# Fan_Motor_Driver.net
KiCad netlist of a schematic drawn in Altium Designer
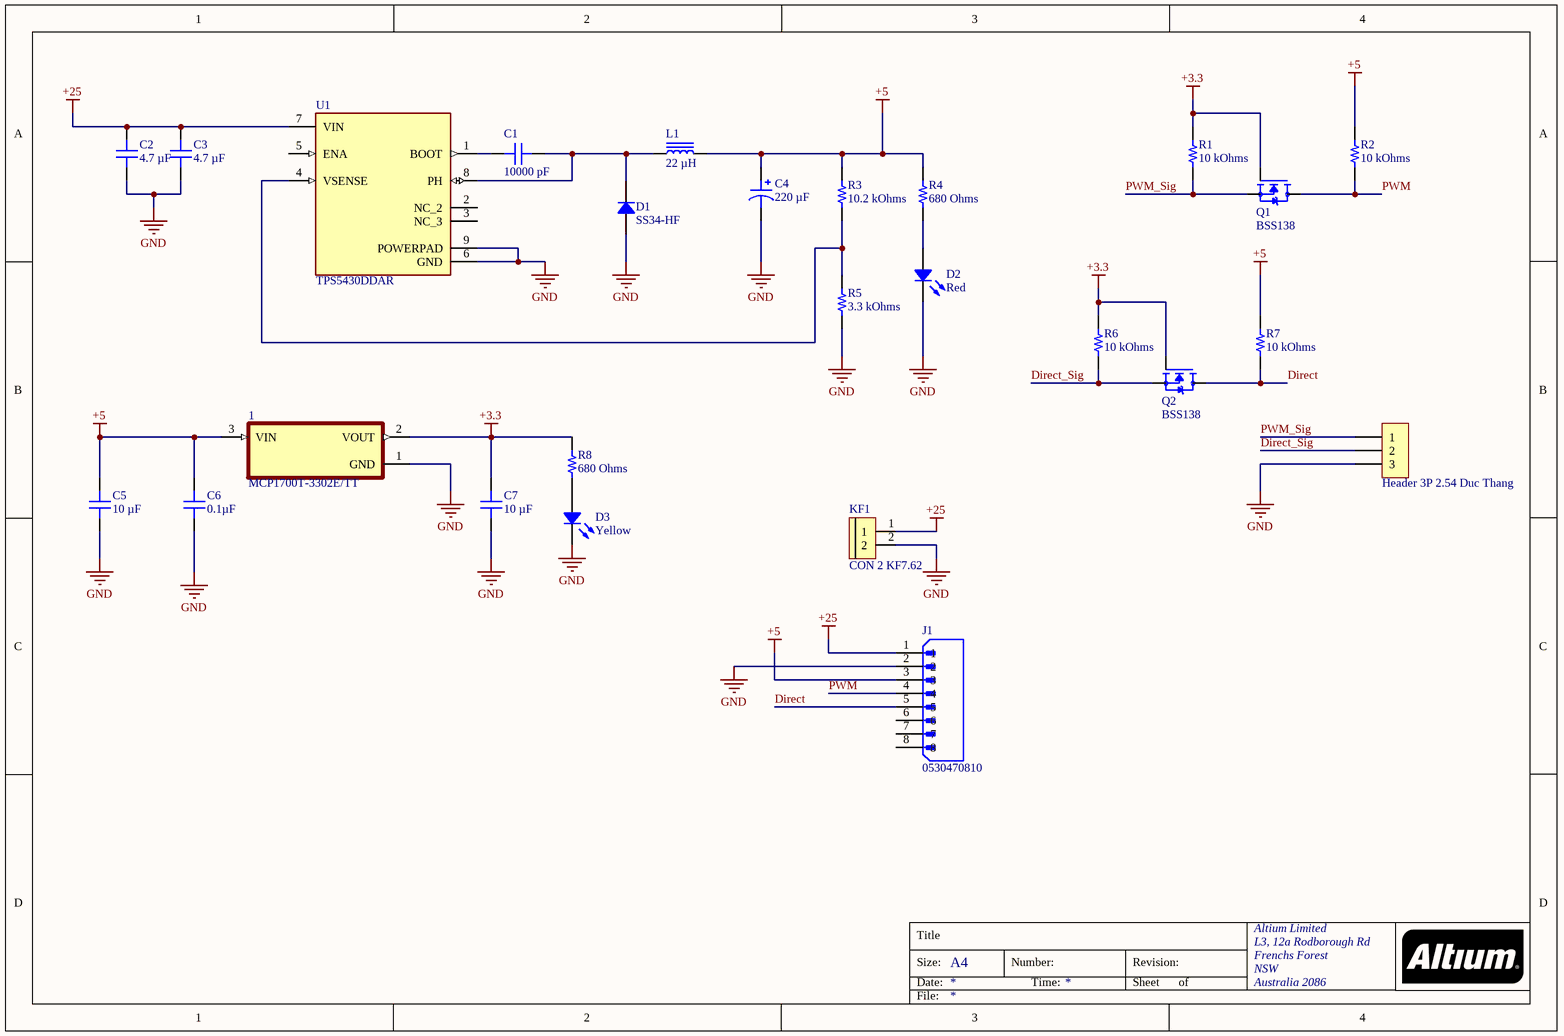
[diagram p0: Fan_Motor_Driver.SchDoc]

(export (version "E")
  (design (tool "Eeschema 10.0.6"))
  (components
    (comp (ref "1")
      (value "MCP1700T-3302E/TT")
      (footprint "SOT95P237X112-3N")
      (description "Linear Voltage Regulator IC 1 Output 250mA SOT-23-3")
      (fields (field (name "MF") "Microchip"))
      (libsource (lib "MCP1700T-3302E_TT") (part "MCP1700T-3302E/TT"))
    )
    (comp (ref "C1")
      (value "10000 pF")
      (footprint "CAP 0603_1608")
      (description "CAP CER 0603 10NF 16V X7R 10%")
      (fields (field (name "PART NUMBER") "C0603C103K4RECAUTO") (field (name "MANUFACTURER") "KEMET"))
      (libsource (lib "Celestial Altium Library - altium_library") (part "Capacitor"))
    )
    (comp (ref "C2")
      (value "4.7 µF")
      (footprint "CAP 0805_2012")
      (description "CAP CER 4.7UF 25V X7R 0805")
      (fields (field (name "PART NUMBER") "KGM21AR71E475KU") (field (name "MANUFACTURER") "KYOCERA AVX"))
      (libsource (lib "Celestial Altium Library - altium_library") (part "Capacitor"))
    )
    (comp (ref "C3")
      (value "4.7 µF")
      (footprint "CAP 0805_2012")
      (description "CAP CER 4.7UF 25V X7R 0805")
      (fields (field (name "PART NUMBER") "KGM21AR71E475KU") (field (name "MANUFACTURER") "KYOCERA AVX"))
      (libsource (lib "Celestial Altium Library - altium_library") (part "Capacitor"))
    )
    (comp (ref "C4")
      (value "220 µF")
      (footprint "CAP ALSMD 6.6MM H6.1MM")
      (description "CAP ALUM 220UF 20% 10V SMD")
      (fields
        (field (name "PART NUMBER") "EEE-FT1A221AL")
        (field (name "MANUFACTURER") "Panasonic Electronic Components")
      )
      (libsource (lib "Celestial Altium Library - altium_library") (part "Polarised Capacitor"))
    )
    (comp (ref "C5")
      (value "10 µF")
      (footprint "CAP 0805_2012")
      (description "CAP CER 10UF 16V X6S 0805")
      (fields
        (field (name "PART NUMBER") "C2012X6S1C106K125AC")
        (field (name "MANUFACTURER") "TDK Corporation")
      )
      (libsource (lib "Celestial Altium Library - altium_library") (part "Capacitor"))
    )
    (comp (ref "C6")
      (value "0.1µF")
      (footprint "CAP 0603_1608")
      (description "CAP CER 0.1UF 16V X7R 0603")
      (fields (field (name "PART NUMBER") "0603YC104K4T4A") (field (name "MANUFACTURER") "AVX Corporation"))
      (libsource (lib "Celestial Altium Library - altium_library") (part "Capacitor"))
    )
    (comp (ref "C7")
      (value "10 µF")
      (footprint "CAP 0805_2012")
      (description "CAP CER 10UF 16V X6S 0805")
      (fields
        (field (name "PART NUMBER") "C2012X6S1C106K125AC")
        (field (name "MANUFACTURER") "TDK Corporation")
      )
      (libsource (lib "Celestial Altium Library - altium_library") (part "Capacitor"))
    )
    (comp (ref "D1")
      (value "SS34-HF")
      (footprint "DO214AC SMA")
      (description "DIODE SCHOTTKY 40V 3A DO214AC")
      (fields (field (name "MANUFACTURER") "Comchip Technology"))
      (libsource (lib "Celestial Altium Library - altium_library") (part "Diode"))
    )
    (comp (ref "D2")
      (value "Red")
      (footprint "LED 0603_1608 RED")
      (description "LED RED DIFFUSED 0603 SMD")
      (fields (field (name "PART NUMBER") "CSL1901VW1") (field (name "MANUFACTURER") "Rohm Semiconductor"))
      (libsource (lib "Celestial Altium Library - altium_library") (part "LED"))
    )
    (comp (ref "D3")
      (value "Yellow")
      (footprint "LED 0603_1608 YELLOW")
      (description "LED YELLOW CLEAR 0603 SMD")
      (fields (field (name "PART NUMBER") "IN-S63AT5Y") (field (name "MANUFACTURER") "Inolux"))
      (libsource (lib "Celestial Altium Library - altium_library") (part "LED"))
    )
    (comp (ref "H1")
      (value "Header 3P 2.54 Duc Thang")
      (footprint "XH2.54M-3")
      (description "Cắm")
      (libsource (lib "Header") (part "Header 3P 2.54 Duc Thang"))
    )
    (comp (ref "J1")
      (value "0530470810")
      (footprint "MOLEX_0530470810")
      (description "Picoblade Connector, 8 Circuit Single Row, Vertical Throughole PCB")
      (fields (field (name "MF") "Molex"))
      (libsource (lib "0530470810") (part "0530470810"))
    )
    (comp (ref "KF1")
      (value "CON 2 KF7.62")
      (footprint "CON 2 KF7.62")
      (description "Cắm")
      (libsource (lib "Connector") (part "CON 2 KF7.62"))
    )
    (comp (ref "L1")
      (value "22 µH")
      (footprint "WURTH WE-LQS 6045")
      (description "FIXED IND 22UH 1.8A 89 MOHM SMD")
      (fields (field (name "PART NUMBER") "74404064220") (field (name "MANUFACTURER") "Würth Elektronik"))
      (libsource (lib "Celestial Altium Library - altium_library") (part "Inductor"))
    )
    (comp (ref "Q1")
      (value "BSS138")
      (footprint "SOT95P240X111-3N")
      (description "N-Channel 50 V 220mA (Ta) 350mW (Ta) Surface Mount SOT-23-3")
      (fields (field (name "MF") "onsemi"))
      (libsource (lib "BSS138") (part "BSS138"))
    )
    (comp (ref "Q2")
      (value "BSS138")
      (footprint "SOT95P240X111-3N")
      (description "N-Channel 50 V 220mA (Ta) 350mW (Ta) Surface Mount SOT-23-3")
      (fields (field (name "MF") "onsemi"))
      (libsource (lib "BSS138") (part "BSS138"))
    )
    (comp (ref "R1")
      (value "10 kOhms")
      (footprint "RES 0603_1608")
      (description "RES SMD 10K OHM 0.1% 1/10W 0603")
      (fields
        (field (name "PART NUMBER") "MCT06030D1002BP100")
        (field (name "MANUFACTURER") "Vishay Beyschlag")
      )
      (libsource (lib "Celestial Altium Library - altium_library") (part "Resistor"))
    )
    (comp (ref "R2")
      (value "10 kOhms")
      (footprint "RES 0603_1608")
      (description "RES SMD 10K OHM 0.1% 1/10W 0603")
      (fields
        (field (name "PART NUMBER") "MCT06030D1002BP100")
        (field (name "MANUFACTURER") "Vishay Beyschlag")
      )
      (libsource (lib "Celestial Altium Library - altium_library") (part "Resistor"))
    )
    (comp (ref "R3")
      (value "10.2 kOhms")
      (footprint "RES 0603_1608")
      (description "RES SMD 10.2KOHM 0.1% 1/16W 0603")
      (fields
        (field (name "PART NUMBER") "CPF0603B10K2E1")
        (field (name "MANUFACTURER") "TE Connectivity Passive Product")
      )
      (libsource (lib "Celestial Altium Library - altium_library") (part "Resistor"))
    )
    (comp (ref "R4")
      (value "680 Ohms")
      (footprint "RES 0603_1608")
      (description "RES SMD 680 OHM 1% 1/3W 0603")
      (fields (field (name "PART NUMBER") "CRCW0603680RFKEAHP") (field (name "MANUFACTURER") "Vishay Dale"))
      (libsource (lib "Celestial Altium Library - altium_library") (part "Resistor"))
    )
    (comp (ref "R5")
      (value "3.3 kOhms")
      (footprint "RES 0603_1608")
      (description "RES 3.3K OHM 5% 1/4W 0603")
      (fields
        (field (name "PART NUMBER") "ERJ-UP3J332V")
        (field (name "MANUFACTURER") "Panasonic Electronic Components")
      )
      (libsource (lib "Celestial Altium Library - altium_library") (part "Resistor"))
    )
    (comp (ref "R6")
      (value "10 kOhms")
      (footprint "RES 0603_1608")
      (description "RES SMD 10K OHM 0.1% 1/10W 0603")
      (fields
        (field (name "PART NUMBER") "MCT06030D1002BP100")
        (field (name "MANUFACTURER") "Vishay Beyschlag")
      )
      (libsource (lib "Celestial Altium Library - altium_library") (part "Resistor"))
    )
    (comp (ref "R7")
      (value "10 kOhms")
      (footprint "RES 0603_1608")
      (description "RES SMD 10K OHM 0.1% 1/10W 0603")
      (fields
        (field (name "PART NUMBER") "MCT06030D1002BP100")
        (field (name "MANUFACTURER") "Vishay Beyschlag")
      )
      (libsource (lib "Celestial Altium Library - altium_library") (part "Resistor"))
    )
    (comp (ref "R8")
      (value "680 Ohms")
      (footprint "RES 0603_1608")
      (description "RES SMD 680 OHM 1% 1/3W 0603")
      (fields (field (name "PART NUMBER") "CRCW0603680RFKEAHP") (field (name "MANUFACTURER") "Vishay Dale"))
      (libsource (lib "Celestial Altium Library - altium_library") (part "Resistor"))
    )
    (comp (ref "U1")
      (value "TPS5430DDAR")
      (footprint "CONV_TPS5430DDAR")
      (description "5.5V to 36V Input, 3A, 500kHz Step-Down Converter")
      (fields (field (name "MF") "Texas Instruments"))
      (libsource (lib "TPS5430DDAR") (part "TPS5430DDAR"))
    )
  )
  (nets
    (net (code "1") (name "+3.3") (class "Default")
      (node (ref "1") (pin "2") (pinfunction "VOUT_2") (pintype "output"))
      (node (ref "C7") (pin "2") (pinfunction "2_2") (pintype "passive"))
      (node (ref "Q1") (pin "1") (pinfunction "G_1") (pintype "passive"))
      (node (ref "Q2") (pin "1") (pinfunction "G_1") (pintype "passive"))
      (node (ref "R1") (pin "2") (pinfunction "2_2") (pintype "passive"))
      (node (ref "R6") (pin "2") (pinfunction "2_2") (pintype "passive"))
      (node (ref "R8") (pin "2") (pinfunction "2_2") (pintype "passive"))
    )
    (net (code "2") (name "+5") (class "Default")
      (node (ref "1") (pin "3") (pinfunction "VIN_3") (pintype "input"))
      (node (ref "C4") (pin "1") (pinfunction "1_1") (pintype "passive"))
      (node (ref "C5") (pin "2") (pinfunction "2_2") (pintype "passive"))
      (node (ref "C6") (pin "2") (pinfunction "2_2") (pintype "passive"))
      (node (ref "J1") (pin "3") (pinfunction "3_3") (pintype "passive"))
      (node (ref "L1") (pin "2") (pinfunction "2_2") (pintype "passive"))
      (node (ref "R2") (pin "2") (pinfunction "2_2") (pintype "passive"))
      (node (ref "R3") (pin "2") (pinfunction "2_2") (pintype "passive"))
      (node (ref "R4") (pin "2") (pinfunction "2_2") (pintype "passive"))
      (node (ref "R7") (pin "2") (pinfunction "2_2") (pintype "passive"))
    )
    (net (code "3") (name "+25") (class "Default")
      (node (ref "C2") (pin "2") (pinfunction "2_2") (pintype "passive"))
      (node (ref "C3") (pin "2") (pinfunction "2_2") (pintype "passive"))
      (node (ref "J1") (pin "1") (pinfunction "1_1") (pintype "passive"))
      (node (ref "KF1") (pin "1") (pinfunction "1_1") (pintype "passive"))
      (node (ref "U1") (pin "7") (pinfunction "VIN_7") (pintype "power_in"))
    )
    (net (code "4") (name "/Direct") (class "Default")
      (node (ref "J1") (pin "5") (pinfunction "5_5") (pintype "passive"))
      (node (ref "Q2") (pin "3") (pinfunction "D_3") (pintype "passive"))
      (node (ref "R7") (pin "1") (pinfunction "1_1") (pintype "passive"))
    )
    (net (code "5") (name "/Direct_Sig") (class "Default")
      (node (ref "H1") (pin "2") (pinfunction "2_2") (pintype "passive"))
      (node (ref "Q2") (pin "2") (pinfunction "S_2") (pintype "passive"))
      (node (ref "R6") (pin "1") (pinfunction "1_1") (pintype "passive"))
    )
    (net (code "6") (name "/PWM") (class "Default")
      (node (ref "J1") (pin "4") (pinfunction "4_4") (pintype "passive"))
      (node (ref "Q1") (pin "3") (pinfunction "D_3") (pintype "passive"))
      (node (ref "R2") (pin "1") (pinfunction "1_1") (pintype "passive"))
    )
    (net (code "7") (name "/PWM_Sig") (class "Default")
      (node (ref "H1") (pin "1") (pinfunction "1_1") (pintype "passive"))
      (node (ref "Q1") (pin "2") (pinfunction "S_2") (pintype "passive"))
      (node (ref "R1") (pin "1") (pinfunction "1_1") (pintype "passive"))
    )
    (net (code "8") (name "GND") (class "Default")
      (node (ref "1") (pin "1") (pinfunction "GND_1") (pintype "power_in"))
      (node (ref "C2") (pin "1") (pinfunction "1_1") (pintype "passive"))
      (node (ref "C3") (pin "1") (pinfunction "1_1") (pintype "passive"))
      (node (ref "C4") (pin "2") (pinfunction "2_2") (pintype "passive"))
      (node (ref "C5") (pin "1") (pinfunction "1_1") (pintype "passive"))
      (node (ref "C6") (pin "1") (pinfunction "1_1") (pintype "passive"))
      (node (ref "C7") (pin "1") (pinfunction "1_1") (pintype "passive"))
      (node (ref "D1") (pin "1") (pinfunction "1_1") (pintype "passive"))
      (node (ref "D2") (pin "2") (pinfunction "2_2") (pintype "passive"))
      (node (ref "D3") (pin "2") (pinfunction "2_2") (pintype "passive"))
      (node (ref "H1") (pin "3") (pinfunction "3_3") (pintype "passive"))
      (node (ref "J1") (pin "2") (pinfunction "2_2") (pintype "passive"))
      (node (ref "KF1") (pin "2") (pinfunction "2_2") (pintype "passive"))
      (node (ref "R5") (pin "1") (pinfunction "1_1") (pintype "passive"))
      (node (ref "U1") (pin "6") (pinfunction "GND_6") (pintype "power_in"))
      (node (ref "U1") (pin "9") (pinfunction "POWERPAD_9") (pintype "power_in"))
    )
    (net (code "9") (name "Net-(D2-Pad1)") (class "Default")
      (node (ref "D2") (pin "1") (pinfunction "1_1") (pintype "passive"))
      (node (ref "R4") (pin "1") (pinfunction "1_1") (pintype "passive"))
    )
    (net (code "10") (name "Net-(D3-Pad1)") (class "Default")
      (node (ref "D3") (pin "1") (pinfunction "1_1") (pintype "passive"))
      (node (ref "R8") (pin "1") (pinfunction "1_1") (pintype "passive"))
    )
    (net (code "11") (name "Net-(U1-BOOT)") (class "Default")
      (node (ref "C1") (pin "2") (pinfunction "2_2") (pintype "passive"))
      (node (ref "U1") (pin "1") (pinfunction "BOOT_1") (pintype "output"))
    )
    (net (code "12") (name "Net-(U1-PH)") (class "Default")
      (node (ref "C1") (pin "1") (pinfunction "1_1") (pintype "passive"))
      (node (ref "D1") (pin "2") (pinfunction "2_2") (pintype "passive"))
      (node (ref "L1") (pin "1") (pinfunction "1_1") (pintype "passive"))
      (node (ref "U1") (pin "8") (pinfunction "PH_8") (pintype "bidirectional"))
    )
    (net (code "13") (name "Net-(U1-VSENSE)") (class "Default")
      (node (ref "R3") (pin "1") (pinfunction "1_1") (pintype "passive"))
      (node (ref "R5") (pin "2") (pinfunction "2_2") (pintype "passive"))
      (node (ref "U1") (pin "4") (pinfunction "VSENSE_4") (pintype "input"))
    )
    (net (code "14") (name "unconnected-(J1-Pad6)") (class "Default")
      (node (ref "J1") (pin "6") (pinfunction "6_6") (pintype "passive"))
    )
    (net (code "15") (name "unconnected-(J1-Pad7)") (class "Default")
      (node (ref "J1") (pin "7") (pinfunction "7_7") (pintype "passive"))
    )
    (net (code "16") (name "unconnected-(J1-Pad8)") (class "Default")
      (node (ref "J1") (pin "8") (pinfunction "8_8") (pintype "passive"))
    )
    (net (code "17") (name "unconnected-(U1-ENA-Pad5)") (class "Default")
      (node (ref "U1") (pin "5") (pinfunction "ENA_5") (pintype "input"))
    )
    (net (code "18") (name "unconnected-(U1-NC_2-Pad2)") (class "Default")
      (node (ref "U1") (pin "2") (pinfunction "NC_2_2") (pintype "passive"))
    )
    (net (code "19") (name "unconnected-(U1-NC_3-Pad3)") (class "Default")
      (node (ref "U1") (pin "3") (pinfunction "NC_3_3") (pintype "passive"))
    )
  )
)
